# GateDriverAndPowerDevices.net
KiCad netlist of a schematic drawn in Altium Designer
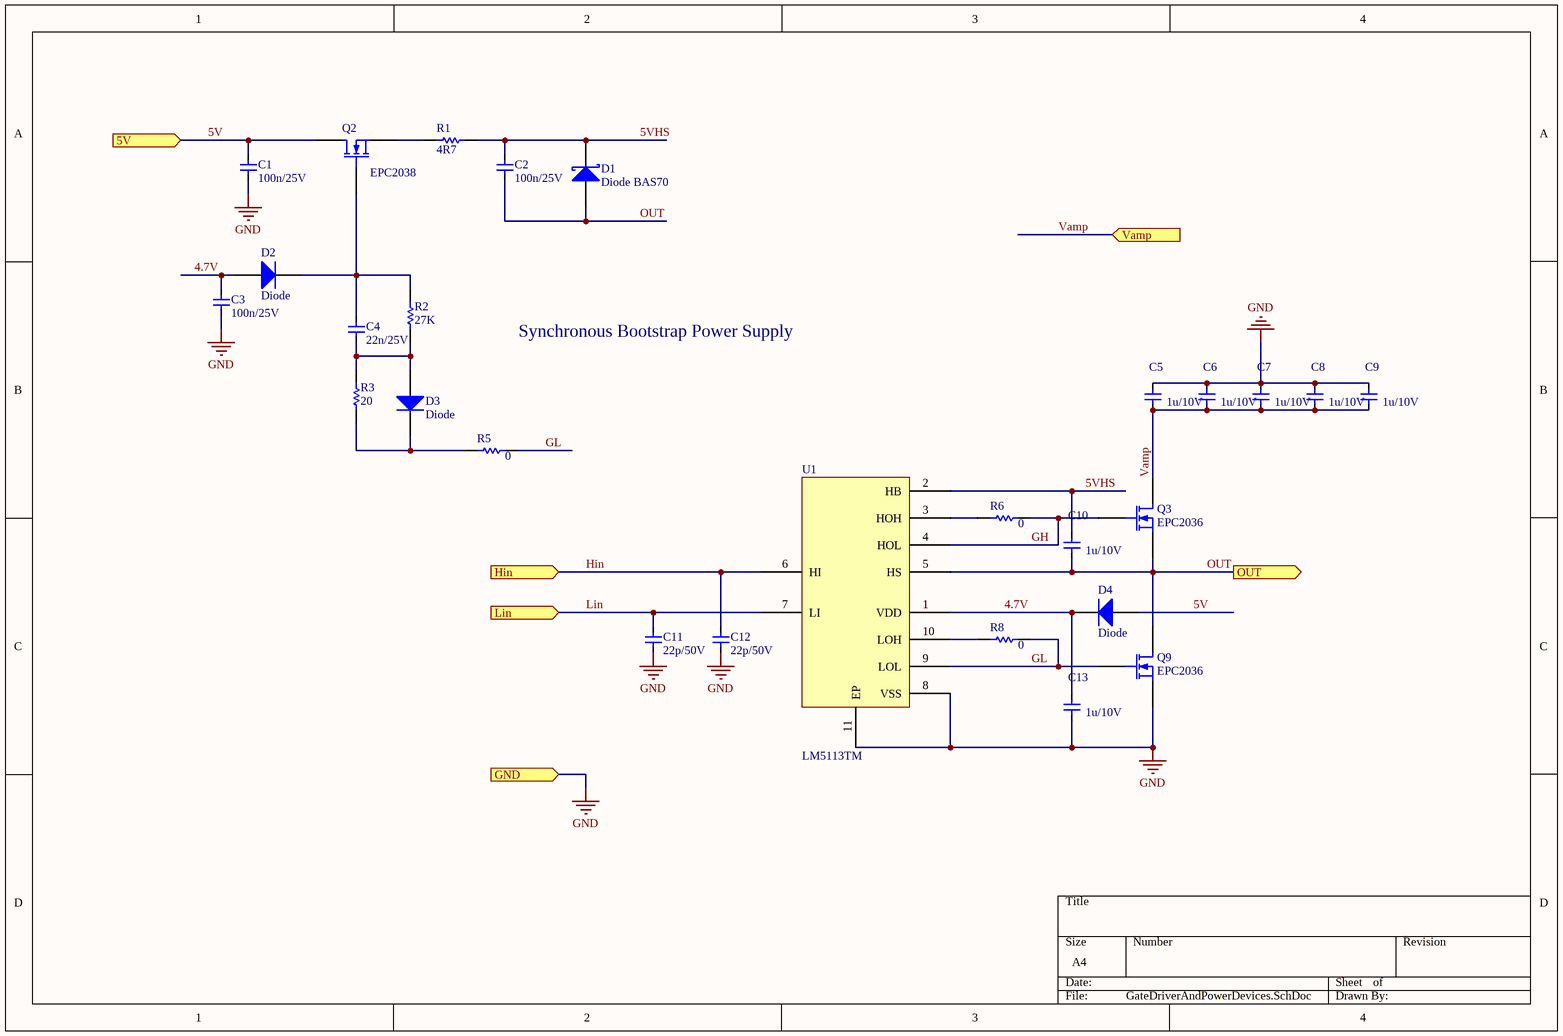
[diagram p0: GateDriverAndPowerDevices.SchDoc]

(export (version "E")
  (design (tool "Eeschema 10.0.6"))
  (components
    (comp (ref "C1")
      (value "100n/25V")
      (footprint "0603")
      (description "Capacitor")
      (libsource (lib "5V1A1.0") (part "CAP1"))
    )
    (comp (ref "C2")
      (value "100n/25V")
      (footprint "0603")
      (description "Capacitor")
      (libsource (lib "5V1A1.0") (part "CAP1"))
    )
    (comp (ref "C3")
      (value "100n/25V")
      (footprint "0603")
      (description "Capacitor")
      (libsource (lib "5V1A1.0") (part "CAP1"))
    )
    (comp (ref "C4")
      (value "22n/25V")
      (footprint "0603")
      (description "Capacitor")
      (libsource (lib "5V1A1.0") (part "CAP1"))
    )
    (comp (ref "C5")
      (value "1u/10V")
      (footprint "0603")
      (description "Capacitor")
      (libsource (lib "5V1A1.0") (part "CAP1"))
    )
    (comp (ref "C6")
      (value "1u/10V")
      (footprint "0603")
      (description "Capacitor")
      (libsource (lib "5V1A1.0") (part "CAP1"))
    )
    (comp (ref "C7")
      (value "1u/10V")
      (footprint "0603")
      (description "Capacitor")
      (libsource (lib "5V1A1.0") (part "CAP1"))
    )
    (comp (ref "C8")
      (value "1u/10V")
      (footprint "0603")
      (description "Capacitor")
      (libsource (lib "5V1A1.0") (part "CAP1"))
    )
    (comp (ref "C9")
      (value "1u/10V")
      (footprint "0603")
      (description "Capacitor")
      (libsource (lib "5V1A1.0") (part "CAP1"))
    )
    (comp (ref "C10")
      (value "1u/10V")
      (footprint "0603")
      (description "Capacitor")
      (libsource (lib "5V1A1.0") (part "CAP1"))
    )
    (comp (ref "C11")
      (value "22p/50V")
      (footprint "0603")
      (description "Capacitor")
      (libsource (lib "5V1A1.0") (part "CAP1"))
    )
    (comp (ref "C12")
      (value "22p/50V")
      (footprint "0603")
      (description "Capacitor")
      (libsource (lib "5V1A1.0") (part "CAP1"))
    )
    (comp (ref "C13")
      (value "1u/10V")
      (footprint "0603")
      (description "Capacitor")
      (libsource (lib "5V1A1.0") (part "CAP1"))
    )
    (comp (ref "D1")
      (value "Diode BAS70")
      (footprint "SMA")
      (description "Silicon AF Schottky Diode for High-Speed Switching")
      (fields (field (name "PUBLISHER") "Altium Limited"))
      (libsource (lib "Miscellaneous Devices") (part "Diode BAS70"))
    )
    (comp (ref "D2")
      (value "Diode")
      (footprint "SMA")
      (description "Default Diode")
      (fields (field (name "PUBLISHER") "Altium Limited"))
      (libsource (lib "Miscellaneous Devices") (part "Diode"))
    )
    (comp (ref "D3")
      (value "Diode")
      (footprint "SMA")
      (description "Default Diode")
      (fields (field (name "PUBLISHER") "Altium Limited"))
      (libsource (lib "Miscellaneous Devices") (part "Diode"))
    )
    (comp (ref "D4")
      (value "Diode")
      (footprint "SMA")
      (description "Default Diode")
      (fields (field (name "PUBLISHER") "Altium Limited"))
      (libsource (lib "Miscellaneous Devices") (part "Diode"))
    )
    (comp (ref "Q2")
      (value "EPC2038")
      (footprint "BGA100P9X9-81A")
      (description "N-Channel MOSFET")
      (fields (field (name "PUBLISHER") "Altium Limited"))
      (libsource (lib "Miscellaneous Devices") (part "MOSFET-N"))
    )
    (comp (ref "Q3")
      (value "EPC2036")
      (footprint "BGA100P9X9-81A")
      (description "N-Channel MOSFET")
      (fields (field (name "PUBLISHER") "Altium Limited"))
      (libsource (lib "Miscellaneous Devices") (part "MOSFET-N"))
    )
    (comp (ref "Q9")
      (value "EPC2036")
      (footprint "BGA100P9X9-81A")
      (description "N-Channel MOSFET")
      (fields (field (name "PUBLISHER") "Altium Limited"))
      (libsource (lib "Miscellaneous Devices") (part "MOSFET-N"))
    )
    (comp (ref "R1")
      (value "4R7")
      (footprint "0603")
      (description "Resistor")
      (fields (field (name "Comment") "Res1") (field (name "PUBLISHER") "Altium Limited"))
      (libsource (lib "Miscellaneous Devices") (part "Res1"))
    )
    (comp (ref "R2")
      (value "27K")
      (footprint "0603")
      (description "Resistor")
      (fields (field (name "Comment") "Res1") (field (name "PUBLISHER") "Altium Limited"))
      (libsource (lib "Miscellaneous Devices") (part "Res1"))
    )
    (comp (ref "R3")
      (value "20")
      (footprint "0603")
      (description "Resistor")
      (fields (field (name "Comment") "Res1") (field (name "PUBLISHER") "Altium Limited"))
      (libsource (lib "Miscellaneous Devices") (part "Res1"))
    )
    (comp (ref "R5")
      (value "0")
      (footprint "0603")
      (description "Resistor")
      (fields (field (name "Comment") "Res1") (field (name "PUBLISHER") "Altium Limited"))
      (libsource (lib "Miscellaneous Devices") (part "Res1"))
    )
    (comp (ref "R6")
      (value "0")
      (footprint "0402")
      (description "Resistor")
      (fields (field (name "Comment") "Res1") (field (name "PUBLISHER") "Altium Limited"))
      (libsource (lib "Miscellaneous Devices") (part "Res1"))
    )
    (comp (ref "R8")
      (value "0")
      (footprint "0402")
      (description "Resistor")
      (fields (field (name "Comment") "Res1") (field (name "PUBLISHER") "Altium Limited"))
      (libsource (lib "Miscellaneous Devices") (part "Res1"))
    )
    (comp (ref "U1")
      (value "LM5113TM")
      (footprint "QFN80P400X400X80-10N")
      (libsource (lib "5V1A1.1") (part "LM5113TM"))
    )
  )
  (nets
    (net (code "1") (name "/4.7V") (class "Default")
      (node (ref "C13") (pin "1") (pinfunction "1_1") (pintype "passive"))
      (node (ref "C3") (pin "1") (pinfunction "1_1") (pintype "passive"))
      (node (ref "D2") (pin "1") (pinfunction "A_1") (pintype "passive"))
      (node (ref "D4") (pin "2") (pinfunction "K_2") (pintype "passive"))
      (node (ref "U1") (pin "1") (pinfunction "VDD_1") (pintype "passive"))
    )
    (net (code "2") (name "/5V") (class "Default")
      (node (ref "C1") (pin "1") (pinfunction "1_1") (pintype "passive"))
      (node (ref "D4") (pin "1") (pinfunction "A_1") (pintype "passive"))
      (node (ref "Q2") (pin "1") (pinfunction "D_1") (pintype "passive"))
    )
    (net (code "3") (name "/5VHS") (class "Default")
      (node (ref "C10") (pin "1") (pinfunction "1_1") (pintype "passive"))
      (node (ref "C2") (pin "1") (pinfunction "1_1") (pintype "passive"))
      (node (ref "D1") (pin "3") (pinfunction "K_3") (pintype "passive"))
      (node (ref "R1") (pin "1") (pinfunction "1_1") (pintype "passive"))
      (node (ref "U1") (pin "2") (pinfunction "HB_2") (pintype "passive"))
    )
    (net (code "4") (name "/GH") (class "Default")
      (node (ref "Q3") (pin "2") (pinfunction "G_2") (pintype "passive"))
      (node (ref "R6") (pin "2") (pinfunction "2_2") (pintype "passive"))
      (node (ref "U1") (pin "4") (pinfunction "HOL_4") (pintype "passive"))
    )
    (net (code "5") (name "/GL") (class "Default")
      (node (ref "Q9") (pin "2") (pinfunction "G_2") (pintype "passive"))
      (node (ref "R5") (pin "2") (pinfunction "2_2") (pintype "passive"))
      (node (ref "R8") (pin "2") (pinfunction "2_2") (pintype "passive"))
      (node (ref "U1") (pin "9") (pinfunction "LOL_9") (pintype "passive"))
    )
    (net (code "6") (name "/Hin") (class "Default")
      (node (ref "C12") (pin "1") (pinfunction "1_1") (pintype "passive"))
      (node (ref "U1") (pin "6") (pinfunction "HI_6") (pintype "passive"))
    )
    (net (code "7") (name "/Lin") (class "Default")
      (node (ref "C11") (pin "1") (pinfunction "1_1") (pintype "passive"))
      (node (ref "U1") (pin "7") (pinfunction "LI_7") (pintype "passive"))
    )
    (net (code "8") (name "/OUT") (class "Default")
      (node (ref "C10") (pin "2") (pinfunction "2_2") (pintype "passive"))
      (node (ref "C2") (pin "2") (pinfunction "2_2") (pintype "passive"))
      (node (ref "D1") (pin "1") (pinfunction "A_1") (pintype "passive"))
      (node (ref "Q3") (pin "3") (pinfunction "S_3") (pintype "passive"))
      (node (ref "Q9") (pin "1") (pinfunction "D_1") (pintype "passive"))
      (node (ref "U1") (pin "5") (pinfunction "HS_5") (pintype "passive"))
    )
    (net (code "9") (name "/Vamp") (class "Default")
      (node (ref "C5") (pin "2") (pinfunction "2_2") (pintype "passive"))
      (node (ref "C6") (pin "2") (pinfunction "2_2") (pintype "passive"))
      (node (ref "C7") (pin "2") (pinfunction "2_2") (pintype "passive"))
      (node (ref "C8") (pin "2") (pinfunction "2_2") (pintype "passive"))
      (node (ref "C9") (pin "2") (pinfunction "2_2") (pintype "passive"))
      (node (ref "Q3") (pin "1") (pinfunction "D_1") (pintype "passive"))
    )
    (net (code "10") (name "GND") (class "Default")
      (node (ref "C1") (pin "2") (pinfunction "2_2") (pintype "passive"))
      (node (ref "C11") (pin "2") (pinfunction "2_2") (pintype "passive"))
      (node (ref "C12") (pin "2") (pinfunction "2_2") (pintype "passive"))
      (node (ref "C13") (pin "2") (pinfunction "2_2") (pintype "passive"))
      (node (ref "C3") (pin "2") (pinfunction "2_2") (pintype "passive"))
      (node (ref "C5") (pin "1") (pinfunction "1_1") (pintype "passive"))
      (node (ref "C6") (pin "1") (pinfunction "1_1") (pintype "passive"))
      (node (ref "C7") (pin "1") (pinfunction "1_1") (pintype "passive"))
      (node (ref "C8") (pin "1") (pinfunction "1_1") (pintype "passive"))
      (node (ref "C9") (pin "1") (pinfunction "1_1") (pintype "passive"))
      (node (ref "Q9") (pin "3") (pinfunction "S_3") (pintype "passive"))
      (node (ref "U1") (pin "11") (pinfunction "EP_11") (pintype "passive"))
      (node (ref "U1") (pin "8") (pinfunction "VSS_8") (pintype "passive"))
    )
    (net (code "11") (name "Net-(D2-K)") (class "Default")
      (node (ref "C4") (pin "1") (pinfunction "1_1") (pintype "passive"))
      (node (ref "D2") (pin "2") (pinfunction "K_2") (pintype "passive"))
      (node (ref "Q2") (pin "2") (pinfunction "G_2") (pintype "passive"))
      (node (ref "R2") (pin "2") (pinfunction "2_2") (pintype "passive"))
    )
    (net (code "12") (name "Net-(D3-A)") (class "Default")
      (node (ref "C4") (pin "2") (pinfunction "2_2") (pintype "passive"))
      (node (ref "D3") (pin "1") (pinfunction "A_1") (pintype "passive"))
      (node (ref "R2") (pin "1") (pinfunction "1_1") (pintype "passive"))
      (node (ref "R3") (pin "2") (pinfunction "2_2") (pintype "passive"))
    )
    (net (code "13") (name "Net-(D3-K)") (class "Default")
      (node (ref "D3") (pin "2") (pinfunction "K_2") (pintype "passive"))
      (node (ref "R3") (pin "1") (pinfunction "1_1") (pintype "passive"))
      (node (ref "R5") (pin "1") (pinfunction "1_1") (pintype "passive"))
    )
    (net (code "14") (name "Net-(Q2-S)") (class "Default")
      (node (ref "Q2") (pin "3") (pinfunction "S_3") (pintype "passive"))
      (node (ref "R1") (pin "2") (pinfunction "2_2") (pintype "passive"))
    )
    (net (code "15") (name "Net-(U1-HOH)") (class "Default")
      (node (ref "R6") (pin "1") (pinfunction "1_1") (pintype "passive"))
      (node (ref "U1") (pin "3") (pinfunction "HOH_3") (pintype "passive"))
    )
    (net (code "16") (name "Net-(U1-LOH)") (class "Default")
      (node (ref "R8") (pin "1") (pinfunction "1_1") (pintype "passive"))
      (node (ref "U1") (pin "10") (pinfunction "LOH_10") (pintype "passive"))
    )
  )
)
